# badge_scienceTour.net
KiCad netlist of a schematic drawn in EAGLE
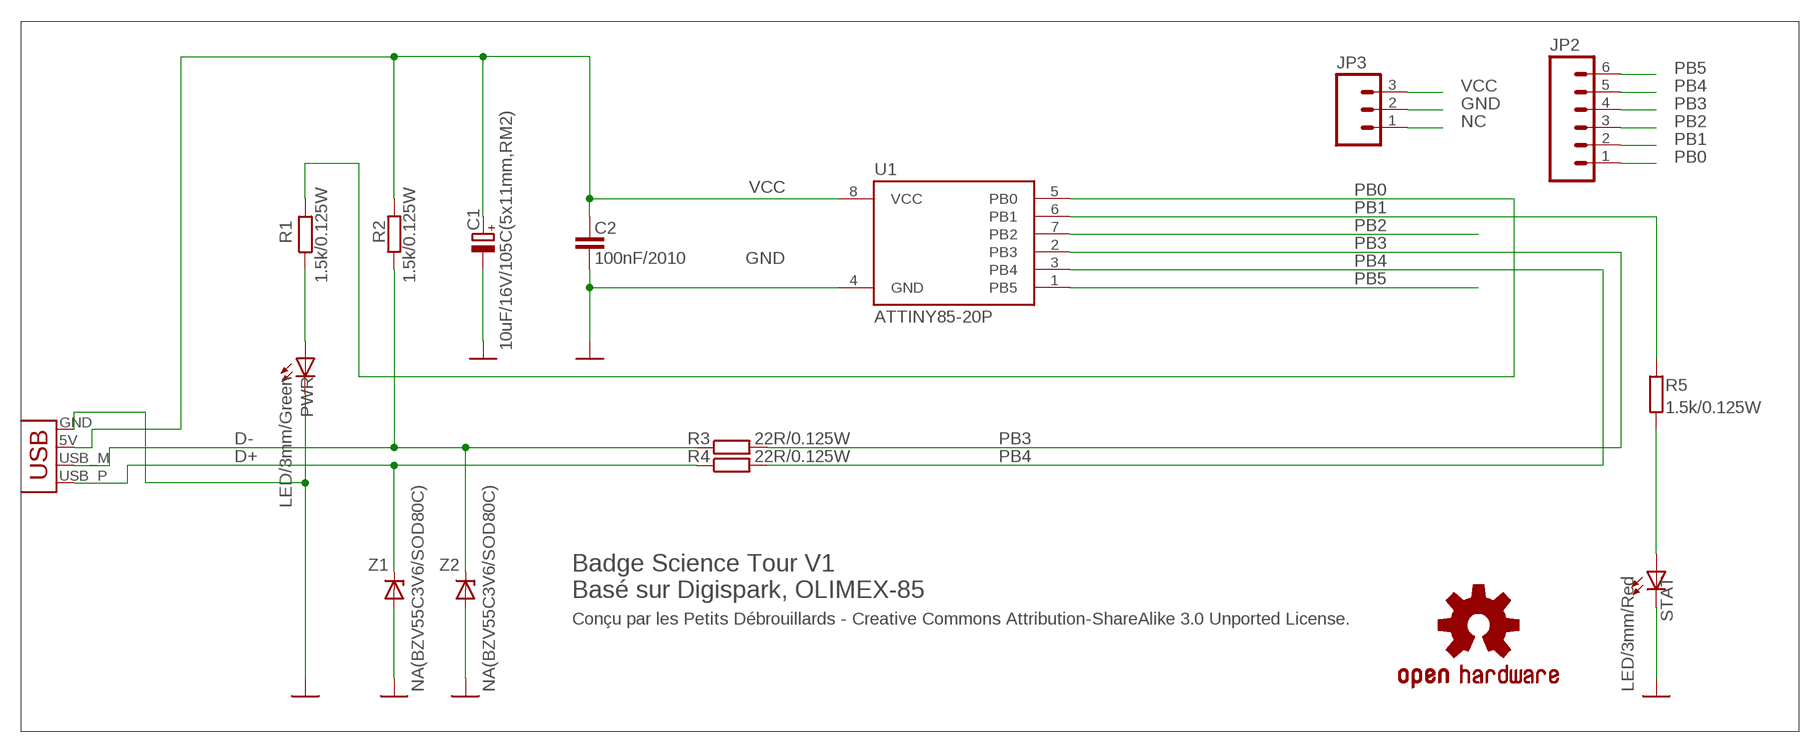
[diagram p0: schematic, sheet 1]

(export (version "E")
  (design (tool "Eeschema 10.0.6"))
  (components
    (comp (ref "C1")
      (value "10uF/16V/105C(5x11mm,RM2)")
      (footprint "eagle-import:E2-5")
      (libsource (lib "eagle-import") (part "CPOL-EUE2-5"))
    )
    (comp (ref "C2")
      (value "100nF/2010")
      (footprint "eagle-import:C025-025X050")
      (libsource (lib "eagle-import") (part "C-EU025-025X050"))
    )
    (comp (ref "JP1")
      (value "USBPCB")
      (footprint "eagle-import:USB-A-PCB")
      (libsource (lib "eagle-import") (part "USBPCB"))
    )
    (comp (ref "JP2")
      (value "M06NO_SILK")
      (footprint "eagle-import:1X06_NO_SILK")
      (libsource (lib "eagle-import") (part "M06NO_SILK"))
    )
    (comp (ref "JP3")
      (value "M031X03_NO_SILK")
      (footprint "eagle-import:1X03_NO_SILK")
      (libsource (lib "eagle-import") (part "M031X03_NO_SILK"))
    )
    (comp (ref "LOGO1")
      (value "OSHW-LOGOS")
      (footprint "eagle-import:OSHW-LOGO-S")
      (libsource (lib "eagle-import") (part "OSHW-LOGOS"))
    )
    (comp (ref "PWR")
      (value "LED/3mm/Green")
      (footprint "eagle-import:LED3MM")
      (libsource (lib "eagle-import") (part "LED3MM"))
    )
    (comp (ref "R1")
      (value "1.5k/0.125W")
      (footprint "eagle-import:0204_5")
      (libsource (lib "eagle-import") (part "R-EU_0204/5"))
    )
    (comp (ref "R2")
      (value "1.5k/0.125W")
      (footprint "eagle-import:0204_5")
      (libsource (lib "eagle-import") (part "R-EU_0204/5"))
    )
    (comp (ref "R3")
      (value "22R/0.125W")
      (footprint "eagle-import:0204_5")
      (libsource (lib "eagle-import") (part "R-EU_0204/5"))
    )
    (comp (ref "R4")
      (value "22R/0.125W")
      (footprint "eagle-import:0204_5")
      (libsource (lib "eagle-import") (part "R-EU_0204/5"))
    )
    (comp (ref "R5")
      (value "1.5k/0.125W")
      (footprint "eagle-import:0204_5")
      (libsource (lib "eagle-import") (part "R-EU_0204/5"))
    )
    (comp (ref "STAT")
      (value "LED/3mm/Red")
      (footprint "eagle-import:LED3MM")
      (libsource (lib "eagle-import") (part "LED3MM"))
    )
    (comp (ref "U1")
      (value "ATTINY85-20P")
      (footprint "eagle-import:PDIP08_300MIL")
      (libsource (lib "eagle-import") (part "ATTINY85P-20"))
    )
    (comp (ref "Z1")
      (value "NA(BZV55C3V6/SOD80C)")
      (footprint "eagle-import:ZDIO-5")
      (libsource (lib "eagle-import") (part "ZENER-DIODEZD-5"))
    )
    (comp (ref "Z2")
      (value "NA(BZV55C3V6/SOD80C)")
      (footprint "eagle-import:ZDIO-5")
      (libsource (lib "eagle-import") (part "ZENER-DIODEZD-5"))
    )
  )
  (nets
    (net (code "1") (name "/D+") (class "Default")
      (node (ref "JP1") (pin "USB_P") (pinfunction "D+_USB_P") (pintype "bidirectional"))
      (node (ref "R4") (pin "1") (pinfunction "1_1") (pintype "passive"))
      (node (ref "Z1") (pin "C") (pinfunction "C_C") (pintype "passive"))
    )
    (net (code "2") (name "/D-") (class "Default")
      (node (ref "JP1") (pin "USB_M") (pinfunction "D-_USB_M") (pintype "bidirectional"))
      (node (ref "R2") (pin "1") (pinfunction "1_1") (pintype "passive"))
      (node (ref "R3") (pin "1") (pinfunction "1_1") (pintype "passive"))
      (node (ref "Z2") (pin "C") (pinfunction "C_C") (pintype "passive"))
    )
    (net (code "3") (name "/NC") (class "Default")
      (node (ref "JP3") (pin "1") (pinfunction "1_1") (pintype "passive"))
    )
    (net (code "4") (name "/PB0") (class "Default")
      (node (ref "JP2") (pin "1") (pinfunction "1_1") (pintype "passive"))
      (node (ref "R1") (pin "2") (pinfunction "2_2") (pintype "passive"))
      (node (ref "U1") (pin "5") (pinfunction "PB0_5") (pintype "bidirectional"))
    )
    (net (code "5") (name "/PB1") (class "Default")
      (node (ref "JP2") (pin "2") (pinfunction "2_2") (pintype "passive"))
      (node (ref "R5") (pin "2") (pinfunction "2_2") (pintype "passive"))
      (node (ref "U1") (pin "6") (pinfunction "PB1_6") (pintype "bidirectional"))
    )
    (net (code "6") (name "/PB2") (class "Default")
      (node (ref "JP2") (pin "3") (pinfunction "3_3") (pintype "passive"))
      (node (ref "U1") (pin "7") (pinfunction "PB2_7") (pintype "bidirectional"))
    )
    (net (code "7") (name "/PB3") (class "Default")
      (node (ref "JP2") (pin "4") (pinfunction "4_4") (pintype "passive"))
      (node (ref "R3") (pin "2") (pinfunction "2_2") (pintype "passive"))
      (node (ref "U1") (pin "2") (pinfunction "PB3_2") (pintype "bidirectional"))
    )
    (net (code "8") (name "/PB4") (class "Default")
      (node (ref "JP2") (pin "5") (pinfunction "5_5") (pintype "passive"))
      (node (ref "R4") (pin "2") (pinfunction "2_2") (pintype "passive"))
      (node (ref "U1") (pin "3") (pinfunction "PB4_3") (pintype "bidirectional"))
    )
    (net (code "9") (name "/PB5") (class "Default")
      (node (ref "JP2") (pin "6") (pinfunction "6_6") (pintype "passive"))
      (node (ref "U1") (pin "1") (pinfunction "PB5_1") (pintype "bidirectional"))
    )
    (net (code "10") (name "/VCC") (class "Default")
      (node (ref "C1") (pin "+") (pinfunction "+_+") (pintype "passive"))
      (node (ref "C2") (pin "1") (pinfunction "1_1") (pintype "passive"))
      (node (ref "JP1") (pin "5V") (pinfunction "VBUS_5V") (pintype "bidirectional"))
      (node (ref "JP3") (pin "3") (pinfunction "3_3") (pintype "passive"))
      (node (ref "R2") (pin "2") (pinfunction "2_2") (pintype "passive"))
      (node (ref "U1") (pin "8") (pinfunction "VCC_8") (pintype "power_in"))
    )
    (net (code "11") (name "GND") (class "Default")
      (node (ref "C1") (pin "-") (pinfunction "-_-") (pintype "passive"))
      (node (ref "C2") (pin "2") (pinfunction "2_2") (pintype "passive"))
      (node (ref "JP1") (pin "GND") (pinfunction "GND_GND") (pintype "bidirectional"))
      (node (ref "JP3") (pin "2") (pinfunction "2_2") (pintype "passive"))
      (node (ref "PWR") (pin "K") (pinfunction "C_K") (pintype "passive"))
      (node (ref "STAT") (pin "K") (pinfunction "C_K") (pintype "passive"))
      (node (ref "U1") (pin "4") (pinfunction "GND_4") (pintype "power_in"))
      (node (ref "Z1") (pin "A") (pinfunction "A_A") (pintype "passive"))
      (node (ref "Z2") (pin "A") (pinfunction "A_A") (pintype "passive"))
    )
    (net (code "12") (name "Net-(PWR-PadA)") (class "Default")
      (node (ref "PWR") (pin "A") (pinfunction "A_A") (pintype "passive"))
      (node (ref "R1") (pin "1") (pinfunction "1_1") (pintype "passive"))
    )
    (net (code "13") (name "Net-(R5-Pad1)") (class "Default")
      (node (ref "R5") (pin "1") (pinfunction "1_1") (pintype "passive"))
      (node (ref "STAT") (pin "A") (pinfunction "A_A") (pintype "passive"))
    )
  )
)
